# MasterMoanna_v13.net
KiCad netlist of a schematic drawn in EAGLE
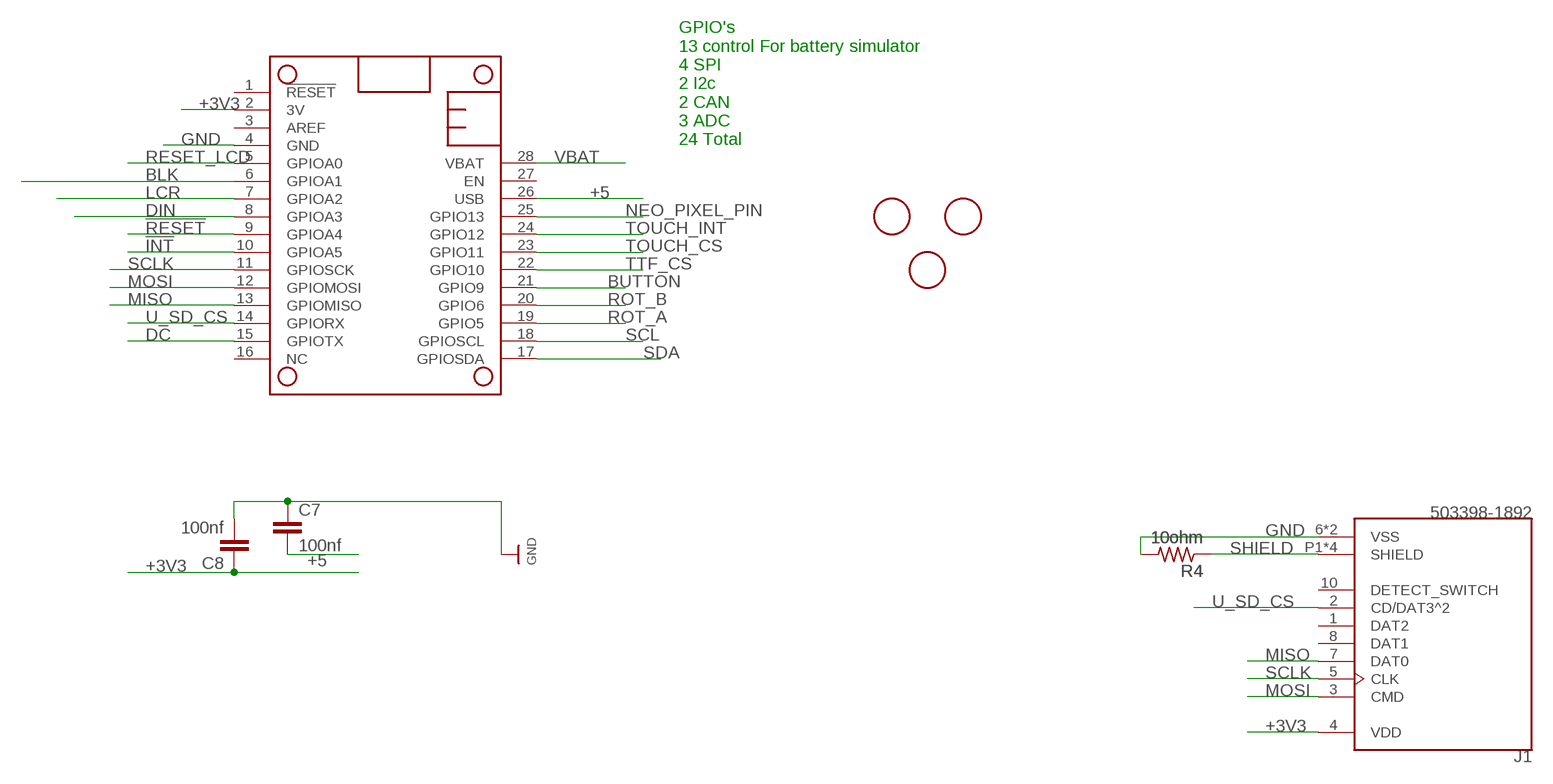
[diagram p0: schematic, sheet 1]
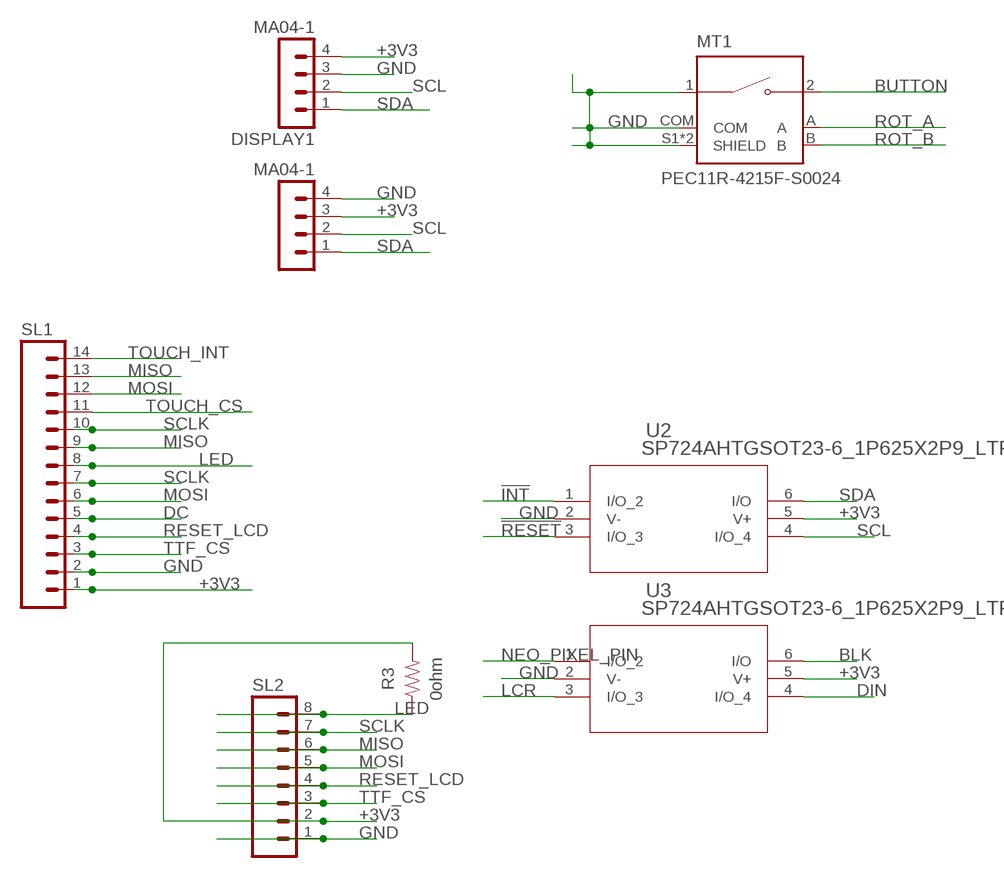
[diagram p1: schematic, sheet 2]
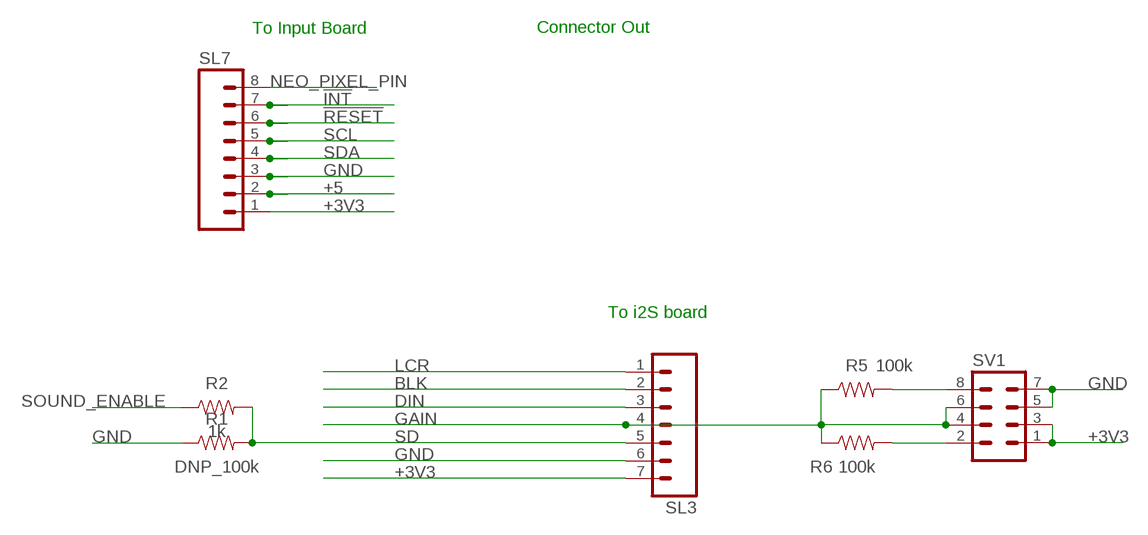
[diagram p2: schematic, sheet 3]

(export (version "E")
  (design (tool "Eeschema 10.0.6"))
  (components
    (comp (ref "C7")
      (value "100nf")
      (footprint "eagle-import:C0805")
      (libsource (lib "eagle-import") (part "C-EUC0805"))
    )
    (comp (ref "C8")
      (value "100nf")
      (footprint "eagle-import:C0805")
      (libsource (lib "eagle-import") (part "C-EUC0805"))
    )
    (comp (ref "FID1")
      (value "FIDUCIAL")
      (footprint "eagle-import:FIDUCIAL_1MM")
      (libsource (lib "eagle-import") (part "FIDUCIAL"))
    )
    (comp (ref "FID2")
      (value "FIDUCIAL")
      (footprint "eagle-import:FIDUCIAL_1MM")
      (libsource (lib "eagle-import") (part "FIDUCIAL"))
    )
    (comp (ref "FID3")
      (value "FIDUCIAL")
      (footprint "eagle-import:FIDUCIAL_1MM")
      (libsource (lib "eagle-import") (part "FIDUCIAL"))
    )
    (comp (ref "J1")
      (value "503398-1892")
      (footprint "eagle-import:MOLEX_503398-1892")
      (fields
        (field (name "DIGI-KEY_PART_NUMBER") "WM11190TR-ND")
        (field (name "MF") "Molex")
        (field (name "MP") "5033981892")
      )
      (libsource (lib "eagle-import") (part "503398-1892"))
    )
    (comp (ref "MS2")
      (value "FEATHERWING_NODIM")
      (footprint "eagle-import:FEATHERWING_DIM")
      (libsource (lib "eagle-import") (part "FEATHERWING_NODIM"))
    )
    (comp (ref "R4")
      (value "10ohm")
      (footprint "eagle-import:M0805")
      (libsource (lib "eagle-import") (part "R-US_M0805"))
    )
    (comp (ref "DISPLAY")
      (value "MA04-1")
      (footprint "eagle-import:MA04-1")
      (libsource (lib "eagle-import") (part "MA04-1"))
    )
    (comp (ref "DISPLAY1")
      (value "MA04-1")
      (footprint "eagle-import:MA04-1")
      (libsource (lib "eagle-import") (part "MA04-1"))
    )
    (comp (ref "MT1")
      (value "PEC11R-4215F-S0024")
      (footprint "eagle-import:XDCR_PEC11R-4215F-S0024")
      (fields (field (name "MF") "Bourns"))
      (libsource (lib "eagle-import") (part "PEC11R-4215F-S0024"))
    )
    (comp (ref "R3")
      (value "0ohm")
      (footprint "eagle-import:RESC2012X65")
      (libsource (lib "eagle-import") (part "R-USCHIP-0805(2012-METRIC)_"))
    )
    (comp (ref "SL1")
      (value "MA14")
      (footprint "eagle-import:14PA")
      (libsource (lib "eagle-import") (part "MA14"))
    )
    (comp (ref "SL2")
      (value "MA08")
      (footprint "eagle-import:08PA")
      (libsource (lib "eagle-import") (part "MA08"))
    )
    (comp (ref "U2")
      (value "SP724AHTGSOT23-6_1P625X2P9_LTF")
      (footprint "eagle-import:SOT23-6_1P625X2P9_LTF")
      (fields
        (field (name "MANUFACTURER_PART_NUMBER") "SP724AHTG")
        (field (name "COPYRIGHT") "Copyright (C) 2022 Ultra Librarian. All rights reserved.")
      )
      (libsource (lib "eagle-import") (part "SP724AHTGSOT23-6_1P625X2P9_LTF"))
    )
    (comp (ref "U3")
      (value "SP724AHTGSOT23-6_1P625X2P9_LTF")
      (footprint "eagle-import:SOT23-6_1P625X2P9_LTF")
      (fields
        (field (name "MANUFACTURER_PART_NUMBER") "SP724AHTG")
        (field (name "COPYRIGHT") "Copyright (C) 2022 Ultra Librarian. All rights reserved.")
      )
      (libsource (lib "eagle-import") (part "SP724AHTGSOT23-6_1P625X2P9_LTF"))
    )
    (comp (ref "R1")
      (value "DNP_100k")
      (footprint "eagle-import:RESC2012X65")
      (libsource (lib "eagle-import") (part "R-USCHIP-0805(2012-METRIC)_"))
    )
    (comp (ref "R2")
      (value "1k")
      (footprint "eagle-import:RESC2012X65")
      (libsource (lib "eagle-import") (part "R-USCHIP-0805(2012-METRIC)_"))
    )
    (comp (ref "R5")
      (value "100k")
      (footprint "eagle-import:RESC2012X65")
      (libsource (lib "eagle-import") (part "R-USCHIP-0805(2012-METRIC)_"))
    )
    (comp (ref "R6")
      (value "100k")
      (footprint "eagle-import:RESC2012X65")
      (libsource (lib "eagle-import") (part "R-USCHIP-0805(2012-METRIC)_"))
    )
    (comp (ref "SL3")
      (value "MA07")
      (footprint "eagle-import:07PA")
      (libsource (lib "eagle-import") (part "MA07"))
    )
    (comp (ref "SL7")
      (value "MA08")
      (footprint "eagle-import:08PA")
      (libsource (lib "eagle-import") (part "con-amp-quick_vf.EHZftIiSSu-FhVI8R5pW5Q_MA08"))
    )
    (comp (ref "SV1")
      (value "MA04-2")
      (footprint "eagle-import:MA04-2")
      (libsource (lib "eagle-import") (part "MA04-2"))
    )
  )
  (nets
    (net (code "1") (name "+3V3") (class "Default")
      (node (ref "C8") (pin "1") (pinfunction "1_1") (pintype "passive"))
      (node (ref "DISPLAY") (pin "3") (pinfunction "C_3") (pintype "passive"))
      (node (ref "DISPLAY1") (pin "4") (pinfunction "D_4") (pintype "passive"))
      (node (ref "J1") (pin "4") (pinfunction "VDD_4") (pintype "power_in"))
      (node (ref "MS2") (pin "2") (pinfunction "3V_2") (pintype "power_in"))
      (node (ref "R3") (pin "2") (pinfunction "2_2") (pintype "passive"))
      (node (ref "SL1") (pin "1") (pinfunction "1_1") (pintype "passive"))
      (node (ref "SL2") (pin "2") (pinfunction "2_2") (pintype "passive"))
      (node (ref "SL3") (pin "7") (pinfunction "7_7") (pintype "passive"))
      (node (ref "SL7") (pin "1") (pinfunction "1_1") (pintype "passive"))
      (node (ref "SV1") (pin "1") (pinfunction "1_1") (pintype "passive"))
      (node (ref "SV1") (pin "3") (pinfunction "3_3") (pintype "passive"))
      (node (ref "U2") (pin "5") (pinfunction "V+_5") (pintype "power_in"))
      (node (ref "U3") (pin "5") (pinfunction "V+_5") (pintype "power_in"))
    )
    (net (code "2") (name "+5") (class "Default")
      (node (ref "C7") (pin "2") (pinfunction "2_2") (pintype "passive"))
      (node (ref "MS2") (pin "26") (pinfunction "USB_26") (pintype "power_in"))
      (node (ref "SL7") (pin "2") (pinfunction "2_2") (pintype "passive"))
    )
    (net (code "3") (name "BLK") (class "Default")
      (node (ref "MS2") (pin "6") (pinfunction "GPIOA1_6") (pintype "bidirectional"))
      (node (ref "SL3") (pin "2") (pinfunction "2_2") (pintype "passive"))
      (node (ref "U3") (pin "6") (pinfunction "I/O_6") (pintype "passive"))
    )
    (net (code "4") (name "BUTTON") (class "Default")
      (node (ref "MS2") (pin "21") (pinfunction "GPIO9_21") (pintype "bidirectional"))
      (node (ref "MT1") (pin "2") (pinfunction "2_2") (pintype "passive"))
    )
    (net (code "5") (name "DC") (class "Default")
      (node (ref "MS2") (pin "15") (pinfunction "GPIOTX_15") (pintype "bidirectional"))
      (node (ref "SL1") (pin "5") (pinfunction "5_5") (pintype "passive"))
    )
    (net (code "6") (name "DIN") (class "Default")
      (node (ref "MS2") (pin "8") (pinfunction "GPIOA3_8") (pintype "bidirectional"))
      (node (ref "SL3") (pin "3") (pinfunction "3_3") (pintype "passive"))
      (node (ref "U3") (pin "4") (pinfunction "I/O_4_4") (pintype "passive"))
    )
    (net (code "7") (name "GAIN") (class "Default")
      (node (ref "R5") (pin "1") (pinfunction "1_1") (pintype "passive"))
      (node (ref "R6") (pin "1") (pinfunction "1_1") (pintype "passive"))
      (node (ref "SL3") (pin "4") (pinfunction "4_4") (pintype "passive"))
      (node (ref "SV1") (pin "4") (pinfunction "4_4") (pintype "passive"))
      (node (ref "SV1") (pin "6") (pinfunction "6_6") (pintype "passive"))
    )
    (net (code "8") (name "GND") (class "Default")
      (node (ref "C7") (pin "1") (pinfunction "1_1") (pintype "passive"))
      (node (ref "C8") (pin "2") (pinfunction "2_2") (pintype "passive"))
      (node (ref "DISPLAY") (pin "4") (pinfunction "D_4") (pintype "passive"))
      (node (ref "DISPLAY1") (pin "3") (pinfunction "C_3") (pintype "passive"))
      (node (ref "J1") (pin "6") (pinfunction "VSS_6") (pintype "power_in"))
      (node (ref "J1") (pin "9") (pinfunction "VSS_9") (pintype "power_in"))
      (node (ref "MS2") (pin "4") (pinfunction "GND_4") (pintype "power_in"))
      (node (ref "MT1") (pin "1") (pinfunction "1_1") (pintype "passive"))
      (node (ref "MT1") (pin "COM") (pinfunction "COM_COM") (pintype "passive"))
      (node (ref "MT1") (pin "S1") (pinfunction "SHIELD_S1") (pintype "passive"))
      (node (ref "MT1") (pin "S2") (pinfunction "SHIELD_S2") (pintype "passive"))
      (node (ref "R1") (pin "1") (pinfunction "1_1") (pintype "passive"))
      (node (ref "R4") (pin "2") (pinfunction "2_2") (pintype "passive"))
      (node (ref "SL1") (pin "2") (pinfunction "2_2") (pintype "passive"))
      (node (ref "SL2") (pin "1") (pinfunction "1_1") (pintype "passive"))
      (node (ref "SL3") (pin "6") (pinfunction "6_6") (pintype "passive"))
      (node (ref "SL7") (pin "3") (pinfunction "3_3") (pintype "passive"))
      (node (ref "SV1") (pin "5") (pinfunction "5_5") (pintype "passive"))
      (node (ref "SV1") (pin "7") (pinfunction "7_7") (pintype "passive"))
      (node (ref "U2") (pin "2") (pinfunction "V-_2") (pintype "power_in"))
      (node (ref "U3") (pin "2") (pinfunction "V-_2") (pintype "power_in"))
    )
    (net (code "9") (name "LCR") (class "Default")
      (node (ref "MS2") (pin "7") (pinfunction "GPIOA2_7") (pintype "bidirectional"))
      (node (ref "SL3") (pin "1") (pinfunction "1_1") (pintype "passive"))
      (node (ref "U3") (pin "3") (pinfunction "I/O_3_3") (pintype "passive"))
    )
    (net (code "10") (name "LED") (class "Default")
      (node (ref "R3") (pin "1") (pinfunction "1_1") (pintype "passive"))
      (node (ref "SL1") (pin "8") (pinfunction "8_8") (pintype "passive"))
      (node (ref "SL2") (pin "8") (pinfunction "8_8") (pintype "passive"))
    )
    (net (code "11") (name "MISO") (class "Default")
      (node (ref "J1") (pin "7") (pinfunction "DAT0_7") (pintype "passive"))
      (node (ref "MS2") (pin "13") (pinfunction "GPIOMISO_13") (pintype "bidirectional"))
      (node (ref "SL1") (pin "13") (pinfunction "13_13") (pintype "passive"))
      (node (ref "SL1") (pin "9") (pinfunction "9_9") (pintype "passive"))
      (node (ref "SL2") (pin "6") (pinfunction "6_6") (pintype "passive"))
    )
    (net (code "12") (name "MOSI") (class "Default")
      (node (ref "J1") (pin "3") (pinfunction "CMD_3") (pintype "passive"))
      (node (ref "MS2") (pin "12") (pinfunction "GPIOMOSI_12") (pintype "bidirectional"))
      (node (ref "SL1") (pin "12") (pinfunction "12_12") (pintype "passive"))
      (node (ref "SL1") (pin "6") (pinfunction "6_6") (pintype "passive"))
      (node (ref "SL2") (pin "5") (pinfunction "5_5") (pintype "passive"))
    )
    (net (code "13") (name "NEO_PIXEL_PIN") (class "Default")
      (node (ref "MS2") (pin "25") (pinfunction "GPIO13_25") (pintype "bidirectional"))
      (node (ref "SL7") (pin "8") (pinfunction "8_8") (pintype "passive"))
      (node (ref "U3") (pin "1") (pinfunction "I/O_2_1") (pintype "passive"))
    )
    (net (code "14") (name "Net-(R5-Pad2)") (class "Default")
      (node (ref "R5") (pin "2") (pinfunction "2_2") (pintype "passive"))
      (node (ref "SV1") (pin "8") (pinfunction "8_8") (pintype "passive"))
    )
    (net (code "15") (name "Net-(R6-Pad2)") (class "Default")
      (node (ref "R6") (pin "2") (pinfunction "2_2") (pintype "passive"))
      (node (ref "SV1") (pin "2") (pinfunction "2_2") (pintype "passive"))
    )
    (net (code "16") (name "RESET_LCD") (class "Default")
      (node (ref "MS2") (pin "5") (pinfunction "GPIOA0_5") (pintype "bidirectional"))
      (node (ref "SL1") (pin "4") (pinfunction "4_4") (pintype "passive"))
      (node (ref "SL2") (pin "4") (pinfunction "4_4") (pintype "passive"))
    )
    (net (code "17") (name "ROT_A") (class "Default")
      (node (ref "MS2") (pin "19") (pinfunction "GPIO5_19") (pintype "bidirectional"))
      (node (ref "MT1") (pin "A") (pinfunction "A_A") (pintype "passive"))
    )
    (net (code "18") (name "ROT_B") (class "Default")
      (node (ref "MS2") (pin "20") (pinfunction "GPIO6_20") (pintype "bidirectional"))
      (node (ref "MT1") (pin "B") (pinfunction "B_B") (pintype "passive"))
    )
    (net (code "19") (name "SCL") (class "Default")
      (node (ref "DISPLAY") (pin "2") (pinfunction "B_2") (pintype "passive"))
      (node (ref "DISPLAY1") (pin "2") (pinfunction "B_2") (pintype "passive"))
      (node (ref "MS2") (pin "18") (pinfunction "GPIOSCL_18") (pintype "bidirectional"))
      (node (ref "SL7") (pin "5") (pinfunction "5_5") (pintype "passive"))
      (node (ref "U2") (pin "4") (pinfunction "I/O_4_4") (pintype "passive"))
    )
    (net (code "20") (name "SCLK") (class "Default")
      (node (ref "J1") (pin "5") (pinfunction "CLK_5") (pintype "passive"))
      (node (ref "MS2") (pin "11") (pinfunction "GPIOSCK_11") (pintype "bidirectional"))
      (node (ref "SL1") (pin "10") (pinfunction "10_10") (pintype "passive"))
      (node (ref "SL1") (pin "7") (pinfunction "7_7") (pintype "passive"))
      (node (ref "SL2") (pin "7") (pinfunction "7_7") (pintype "passive"))
    )
    (net (code "21") (name "SD") (class "Default")
      (node (ref "R1") (pin "2") (pinfunction "2_2") (pintype "passive"))
      (node (ref "R2") (pin "2") (pinfunction "2_2") (pintype "passive"))
      (node (ref "SL3") (pin "5") (pinfunction "5_5") (pintype "passive"))
    )
    (net (code "22") (name "SDA") (class "Default")
      (node (ref "DISPLAY") (pin "1") (pinfunction "A_1") (pintype "passive"))
      (node (ref "DISPLAY1") (pin "1") (pinfunction "A_1") (pintype "passive"))
      (node (ref "MS2") (pin "17") (pinfunction "GPIOSDA_17") (pintype "bidirectional"))
      (node (ref "SL7") (pin "4") (pinfunction "4_4") (pintype "passive"))
      (node (ref "U2") (pin "6") (pinfunction "I/O_6") (pintype "passive"))
    )
    (net (code "23") (name "SHIELD") (class "Default")
      (node (ref "J1") (pin "P1") (pinfunction "SHIELD_P1") (pintype "passive"))
      (node (ref "J1") (pin "P2") (pinfunction "SHIELD_P2") (pintype "passive"))
      (node (ref "J1") (pin "P3") (pinfunction "SHIELD_P3") (pintype "passive"))
      (node (ref "J1") (pin "P4") (pinfunction "SHIELD_P4") (pintype "passive"))
      (node (ref "R4") (pin "1") (pinfunction "1_1") (pintype "passive"))
    )
    (net (code "24") (name "SOUND_ENABLE") (class "Default")
      (node (ref "R2") (pin "1") (pinfunction "1_1") (pintype "passive"))
    )
    (net (code "25") (name "TOUCH_CS") (class "Default")
      (node (ref "MS2") (pin "23") (pinfunction "GPIO11_23") (pintype "bidirectional"))
      (node (ref "SL1") (pin "11") (pinfunction "11_11") (pintype "passive"))
    )
    (net (code "26") (name "TOUCH_INT") (class "Default")
      (node (ref "MS2") (pin "24") (pinfunction "GPIO12_24") (pintype "bidirectional"))
      (node (ref "SL1") (pin "14") (pinfunction "14_14") (pintype "passive"))
    )
    (net (code "27") (name "TTF_CS") (class "Default")
      (node (ref "MS2") (pin "22") (pinfunction "GPIO10_22") (pintype "bidirectional"))
      (node (ref "SL1") (pin "3") (pinfunction "3_3") (pintype "passive"))
      (node (ref "SL2") (pin "3") (pinfunction "3_3") (pintype "passive"))
    )
    (net (code "28") (name "U_SD_CS") (class "Default")
      (node (ref "J1") (pin "2") (pinfunction "CD/DAT3^2_2") (pintype "passive"))
      (node (ref "MS2") (pin "14") (pinfunction "GPIORX_14") (pintype "bidirectional"))
    )
    (net (code "29") (name "VBAT") (class "Default")
      (node (ref "MS2") (pin "28") (pinfunction "VBAT_28") (pintype "power_in"))
    )
    (net (code "30") (name "unconnected-(J1-DAT1-Pad8)") (class "Default")
      (node (ref "J1") (pin "8") (pinfunction "DAT1_8") (pintype "passive"))
    )
    (net (code "31") (name "unconnected-(J1-DAT2-Pad1)") (class "Default")
      (node (ref "J1") (pin "1") (pinfunction "DAT2_1") (pintype "passive"))
    )
    (net (code "32") (name "unconnected-(J1-DETECT_SWITCH-Pad10)") (class "Default")
      (node (ref "J1") (pin "10") (pinfunction "DETECT_SWITCH_10") (pintype "passive"))
    )
    (net (code "33") (name "unconnected-(MS2-AREF-Pad3)") (class "Default")
      (node (ref "MS2") (pin "3") (pinfunction "AREF_3") (pintype "passive"))
    )
    (net (code "34") (name "unconnected-(MS2-EN-Pad27)") (class "Default")
      (node (ref "MS2") (pin "27") (pinfunction "EN_27") (pintype "passive"))
    )
    (net (code "35") (name "unconnected-(MS2-NC-Pad16)") (class "Default")
      (node (ref "MS2") (pin "16") (pinfunction "NC_16") (pintype "passive"))
    )
    (net (code "36") (name "unconnected-(MS2-~{RESET}-Pad1)") (class "Default")
      (node (ref "MS2") (pin "1") (pinfunction "~{RESET}_1") (pintype "input"))
    )
    (net (code "37") (name "~{INT}") (class "Default")
      (node (ref "MS2") (pin "10") (pinfunction "GPIOA5_10") (pintype "bidirectional"))
      (node (ref "SL7") (pin "7") (pinfunction "7_7") (pintype "passive"))
      (node (ref "U2") (pin "1") (pinfunction "I/O_2_1") (pintype "passive"))
    )
    (net (code "38") (name "~{RESET}") (class "Default")
      (node (ref "MS2") (pin "9") (pinfunction "GPIOA4_9") (pintype "bidirectional"))
      (node (ref "SL7") (pin "6") (pinfunction "6_6") (pintype "passive"))
      (node (ref "U2") (pin "3") (pinfunction "I/O_3_3") (pintype "passive"))
    )
  )
)
